# Yay_n_Ders_1.net
KiCad netlist of a schematic drawn in EAGLE
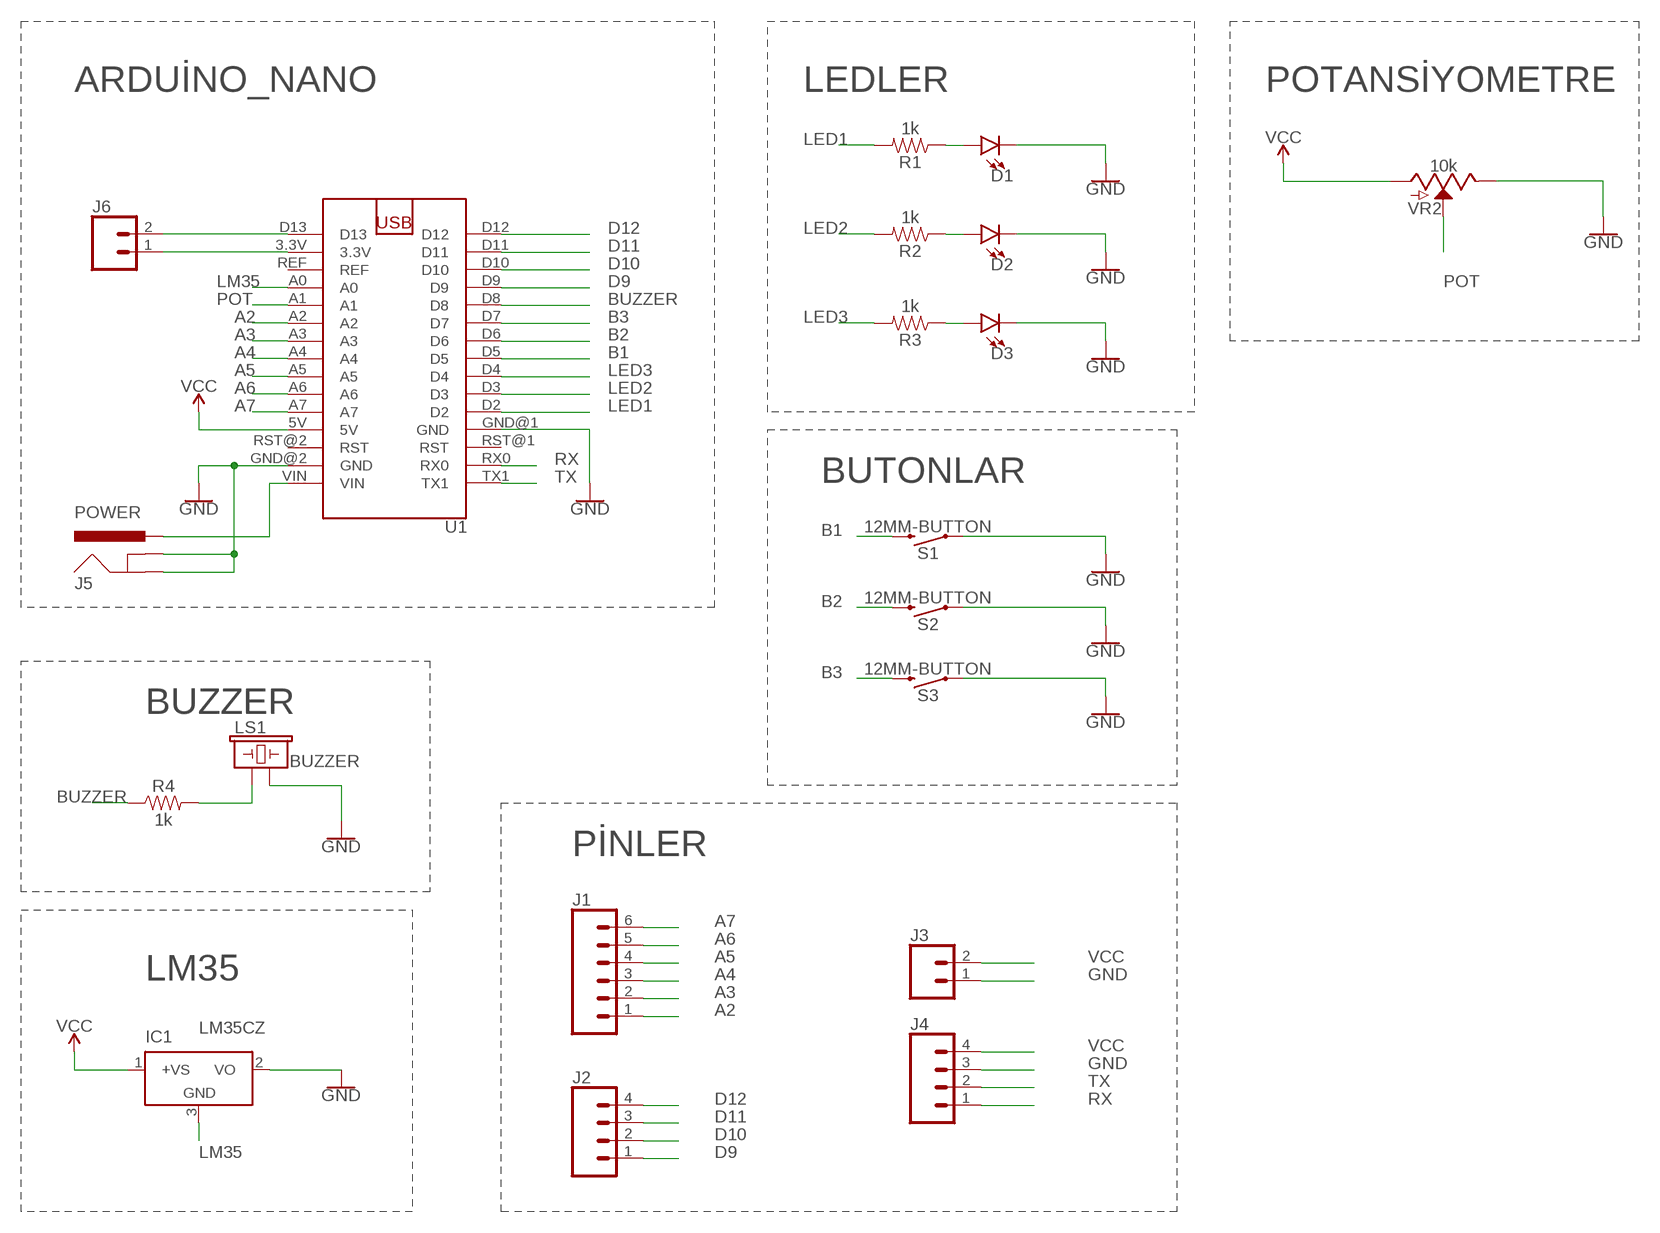
[diagram p0: schematic, sheet 1]

(export (version "E")
  (design (tool "Eeschema 10.0.6"))
  (components
    (comp (ref "D1")
      (value "LED-3MM-NO_SILK")
      (footprint "eagle-import:LED_3MM-NS")
      (libsource (lib "eagle-import") (part "LED-3MM-NO_SILK"))
    )
    (comp (ref "D2")
      (value "LED-3MM-NO_SILK")
      (footprint "eagle-import:LED_3MM-NS")
      (libsource (lib "eagle-import") (part "LED-3MM-NO_SILK"))
    )
    (comp (ref "D3")
      (value "LED-3MM-NO_SILK")
      (footprint "eagle-import:LED_3MM-NS")
      (libsource (lib "eagle-import") (part "LED-3MM-NO_SILK"))
    )
    (comp (ref "IC1")
      (value "LM35CZ")
      (footprint "eagle-import:TO92")
      (libsource (lib "eagle-import") (part "LM35CZ"))
    )
    (comp (ref "J1")
      (value "CONN_06LOCK")
      (footprint "eagle-import:1X06_LOCK")
      (libsource (lib "eagle-import") (part "CONN_06LOCK"))
    )
    (comp (ref "J2")
      (value "CONN_04")
      (footprint "eagle-import:1X04")
      (libsource (lib "eagle-import") (part "CONN_04"))
    )
    (comp (ref "J3")
      (value "CONN_02")
      (footprint "eagle-import:1X02")
      (libsource (lib "eagle-import") (part "CONN_02"))
    )
    (comp (ref "J4")
      (value "CONN_04")
      (footprint "eagle-import:1X04")
      (libsource (lib "eagle-import") (part "CONN_04"))
    )
    (comp (ref "J5")
      (value "POWER")
      (footprint "eagle-import:POWER_JACK_PTH")
      (libsource (lib "eagle-import") (part "POWER_JACK"))
    )
    (comp (ref "J6")
      (value "CONN_02")
      (footprint "eagle-import:1X02")
      (libsource (lib "eagle-import") (part "CONN_02"))
    )
    (comp (ref "LS1")
      (value "BUZZER")
      (footprint "eagle-import:BUZZER-12MM")
      (libsource (lib "eagle-import") (part "BUZZER-PTH"))
    )
    (comp (ref "R1")
      (value "1k")
      (footprint "eagle-import:AXIAL-0.3")
      (libsource (lib "eagle-import") (part "1KOHM-HORIZ-1/4W-1%"))
    )
    (comp (ref "R2")
      (value "1k")
      (footprint "eagle-import:AXIAL-0.3")
      (libsource (lib "eagle-import") (part "1KOHM-HORIZ-1/4W-1%"))
    )
    (comp (ref "R3")
      (value "1k")
      (footprint "eagle-import:AXIAL-0.3")
      (libsource (lib "eagle-import") (part "1KOHM-HORIZ-1/4W-1%"))
    )
    (comp (ref "R4")
      (value "1k")
      (footprint "eagle-import:AXIAL-0.3")
      (libsource (lib "eagle-import") (part "1KOHM-HORIZ-1/4W-1%"))
    )
    (comp (ref "S1")
      (value "12MM-BUTTON")
      (footprint "eagle-import:TACTILE_SWITCH_PTH_12MM")
      (libsource (lib "eagle-import") (part "MOMENTARY-SWITCH-SPST-PTH-12MM"))
    )
    (comp (ref "S2")
      (value "12MM-BUTTON")
      (footprint "eagle-import:TACTILE_SWITCH_PTH_12MM")
      (libsource (lib "eagle-import") (part "MOMENTARY-SWITCH-SPST-PTH-12MM"))
    )
    (comp (ref "S3")
      (value "12MM-BUTTON")
      (footprint "eagle-import:TACTILE_SWITCH_PTH_12MM")
      (libsource (lib "eagle-import") (part "MOMENTARY-SWITCH-SPST-PTH-12MM"))
    )
    (comp (ref "U1")
      (value "ARDUINO_NANO")
      (footprint "eagle-import:ARDUINO_NANO")
      (libsource (lib "eagle-import") (part "ARDUINO_NANO"))
    )
    (comp (ref "VR2")
      (value "10k")
      (footprint "eagle-import:POT-PTH-ALPS")
      (libsource (lib "eagle-import") (part "POTENTIOMETER-PTH-9MM-1/20W-20%"))
    )
  )
  (nets
    (net (code "1") (name "/A2") (class "Default")
      (node (ref "J1") (pin "1") (pinfunction "1_1") (pintype "passive"))
      (node (ref "U1") (pin "A2") (pinfunction "A2_A2") (pintype "bidirectional"))
    )
    (net (code "2") (name "/A3") (class "Default")
      (node (ref "J1") (pin "2") (pinfunction "2_2") (pintype "passive"))
      (node (ref "U1") (pin "A3") (pinfunction "A3_A3") (pintype "bidirectional"))
    )
    (net (code "3") (name "/A4") (class "Default")
      (node (ref "J1") (pin "3") (pinfunction "3_3") (pintype "passive"))
      (node (ref "U1") (pin "A4") (pinfunction "A4_A4") (pintype "bidirectional"))
    )
    (net (code "4") (name "/A5") (class "Default")
      (node (ref "J1") (pin "4") (pinfunction "4_4") (pintype "passive"))
      (node (ref "U1") (pin "A5") (pinfunction "A5_A5") (pintype "bidirectional"))
    )
    (net (code "5") (name "/A6") (class "Default")
      (node (ref "J1") (pin "5") (pinfunction "5_5") (pintype "passive"))
      (node (ref "U1") (pin "A6") (pinfunction "A6_A6") (pintype "bidirectional"))
    )
    (net (code "6") (name "/A7") (class "Default")
      (node (ref "J1") (pin "6") (pinfunction "6_6") (pintype "passive"))
      (node (ref "U1") (pin "A7") (pinfunction "A7_A7") (pintype "bidirectional"))
    )
    (net (code "7") (name "/B1") (class "Default")
      (node (ref "S1") (pin "3") (pinfunction "2_3") (pintype "passive"))
      (node (ref "U1") (pin "D5") (pinfunction "D5_D5") (pintype "bidirectional"))
    )
    (net (code "8") (name "/B2") (class "Default")
      (node (ref "S2") (pin "3") (pinfunction "2_3") (pintype "passive"))
      (node (ref "U1") (pin "D6") (pinfunction "D6_D6") (pintype "bidirectional"))
    )
    (net (code "9") (name "/B3") (class "Default")
      (node (ref "S3") (pin "3") (pinfunction "2_3") (pintype "passive"))
      (node (ref "U1") (pin "D7") (pinfunction "D7_D7") (pintype "bidirectional"))
    )
    (net (code "10") (name "/BUZZER") (class "Default")
      (node (ref "R4") (pin "P$1") (pinfunction "1_P$1") (pintype "passive"))
      (node (ref "U1") (pin "D8") (pinfunction "D8_D8") (pintype "bidirectional"))
    )
    (net (code "11") (name "/D9") (class "Default")
      (node (ref "J2") (pin "1") (pinfunction "1_1") (pintype "passive"))
      (node (ref "U1") (pin "D9") (pinfunction "D9_D9") (pintype "bidirectional"))
    )
    (net (code "12") (name "/D10") (class "Default")
      (node (ref "J2") (pin "2") (pinfunction "2_2") (pintype "passive"))
      (node (ref "U1") (pin "D10") (pinfunction "D10_D10") (pintype "bidirectional"))
    )
    (net (code "13") (name "/D11") (class "Default")
      (node (ref "J2") (pin "3") (pinfunction "3_3") (pintype "passive"))
      (node (ref "U1") (pin "D11") (pinfunction "D11_D11") (pintype "bidirectional"))
    )
    (net (code "14") (name "/D12") (class "Default")
      (node (ref "J2") (pin "4") (pinfunction "4_4") (pintype "passive"))
      (node (ref "U1") (pin "D12") (pinfunction "D12_D12") (pintype "bidirectional"))
    )
    (net (code "15") (name "/LED1") (class "Default")
      (node (ref "R1") (pin "P$2") (pinfunction "2_P$2") (pintype "passive"))
      (node (ref "U1") (pin "D2") (pinfunction "D2_D2") (pintype "bidirectional"))
    )
    (net (code "16") (name "/LED2") (class "Default")
      (node (ref "R2") (pin "P$2") (pinfunction "2_P$2") (pintype "passive"))
      (node (ref "U1") (pin "D3") (pinfunction "D3_D3") (pintype "bidirectional"))
    )
    (net (code "17") (name "/LED3") (class "Default")
      (node (ref "R3") (pin "P$2") (pinfunction "2_P$2") (pintype "passive"))
      (node (ref "U1") (pin "D4") (pinfunction "D4_D4") (pintype "bidirectional"))
    )
    (net (code "18") (name "/LM35") (class "Default")
      (node (ref "IC1") (pin "3") (pinfunction "GND_3") (pintype "power_in"))
      (node (ref "U1") (pin "A0") (pinfunction "A0_A0") (pintype "bidirectional"))
    )
    (net (code "19") (name "/POT") (class "Default")
      (node (ref "U1") (pin "A1") (pinfunction "A1_A1") (pintype "bidirectional"))
      (node (ref "VR2") (pin "P$2") (pinfunction "S_P$2") (pintype "passive"))
    )
    (net (code "20") (name "/RX") (class "Default")
      (node (ref "J4") (pin "1") (pinfunction "1_1") (pintype "passive"))
      (node (ref "U1") (pin "RX0") (pinfunction "RX0_RX0") (pintype "bidirectional"))
    )
    (net (code "21") (name "/TX") (class "Default")
      (node (ref "J4") (pin "2") (pinfunction "2_2") (pintype "passive"))
      (node (ref "U1") (pin "TX1") (pinfunction "TX1_TX1") (pintype "bidirectional"))
    )
    (net (code "22") (name "GND") (class "Default")
      (node (ref "D1") (pin "K") (pinfunction "C_K") (pintype "passive"))
      (node (ref "D2") (pin "K") (pinfunction "C_K") (pintype "passive"))
      (node (ref "D3") (pin "K") (pinfunction "C_K") (pintype "passive"))
      (node (ref "IC1") (pin "2") (pinfunction "VO_2") (pintype "input"))
      (node (ref "J3") (pin "1") (pinfunction "1_1") (pintype "passive"))
      (node (ref "J4") (pin "3") (pinfunction "3_3") (pintype "passive"))
      (node (ref "J5") (pin "GND") (pinfunction "GND_GND") (pintype "bidirectional"))
      (node (ref "J5") (pin "GNDBREAK") (pinfunction "GNDBREAK_GNDBREAK") (pintype "bidirectional"))
      (node (ref "LS1") (pin "-") (pinfunction "2_-") (pintype "passive"))
      (node (ref "S1") (pin "1") (pinfunction "1_1") (pintype "passive"))
      (node (ref "S2") (pin "1") (pinfunction "1_1") (pintype "passive"))
      (node (ref "S3") (pin "1") (pinfunction "1_1") (pintype "passive"))
      (node (ref "U1") (pin "GND@1") (pinfunction "GND_GND@1") (pintype "bidirectional"))
      (node (ref "U1") (pin "GND@2") (pinfunction "GND_GND@2") (pintype "bidirectional"))
      (node (ref "VR2") (pin "P$1") (pinfunction "E_P$1") (pintype "passive"))
    )
    (net (code "23") (name "Net-(J5-PadPWR)") (class "Default")
      (node (ref "J5") (pin "PWR") (pinfunction "PWR_PWR") (pintype "bidirectional"))
      (node (ref "U1") (pin "VIN") (pinfunction "VIN_VIN") (pintype "bidirectional"))
    )
    (net (code "24") (name "Net-(J6-Pad1)") (class "Default")
      (node (ref "J6") (pin "1") (pinfunction "1_1") (pintype "passive"))
      (node (ref "U1") (pin "3.3V") (pinfunction "3.3V_3.3V") (pintype "bidirectional"))
    )
    (net (code "25") (name "Net-(J6-Pad2)") (class "Default")
      (node (ref "J6") (pin "2") (pinfunction "2_2") (pintype "passive"))
      (node (ref "U1") (pin "D13") (pinfunction "D13_D13") (pintype "bidirectional"))
    )
    (net (code "26") (name "Net-(LS1-1)") (class "Default")
      (node (ref "LS1") (pin "+") (pinfunction "1_+") (pintype "passive"))
      (node (ref "R4") (pin "P$2") (pinfunction "2_P$2") (pintype "passive"))
    )
    (net (code "27") (name "Net-(R1-1)") (class "Default")
      (node (ref "D1") (pin "A") (pinfunction "A_A") (pintype "passive"))
      (node (ref "R1") (pin "P$1") (pinfunction "1_P$1") (pintype "passive"))
    )
    (net (code "28") (name "Net-(R2-1)") (class "Default")
      (node (ref "D2") (pin "A") (pinfunction "A_A") (pintype "passive"))
      (node (ref "R2") (pin "P$1") (pinfunction "1_P$1") (pintype "passive"))
    )
    (net (code "29") (name "Net-(R3-1)") (class "Default")
      (node (ref "D3") (pin "A") (pinfunction "A_A") (pintype "passive"))
      (node (ref "R3") (pin "P$1") (pinfunction "1_P$1") (pintype "passive"))
    )
    (net (code "30") (name "VCC") (class "Default")
      (node (ref "IC1") (pin "1") (pinfunction "+VS_1") (pintype "input"))
      (node (ref "J3") (pin "2") (pinfunction "2_2") (pintype "passive"))
      (node (ref "J4") (pin "4") (pinfunction "4_4") (pintype "passive"))
      (node (ref "U1") (pin "5V") (pinfunction "5V_5V") (pintype "bidirectional"))
      (node (ref "VR2") (pin "P$3") (pinfunction "A_P$3") (pintype "passive"))
    )
    (net (code "31") (name "unconnected-(U1-PadREF)") (class "Default")
      (node (ref "U1") (pin "REF") (pinfunction "REF_REF") (pintype "bidirectional"))
    )
    (net (code "32") (name "unconnected-(U1-RST-PadRST@1)") (class "Default")
      (node (ref "U1") (pin "RST@1") (pinfunction "RST_RST@1") (pintype "bidirectional"))
    )
    (net (code "33") (name "unconnected-(U1-RST-PadRST@2)") (class "Default")
      (node (ref "U1") (pin "RST@2") (pinfunction "RST_RST@2") (pintype "bidirectional"))
    )
  )
)
